# 09-other.net
KiCad netlist of a schematic drawn in Altium Designer
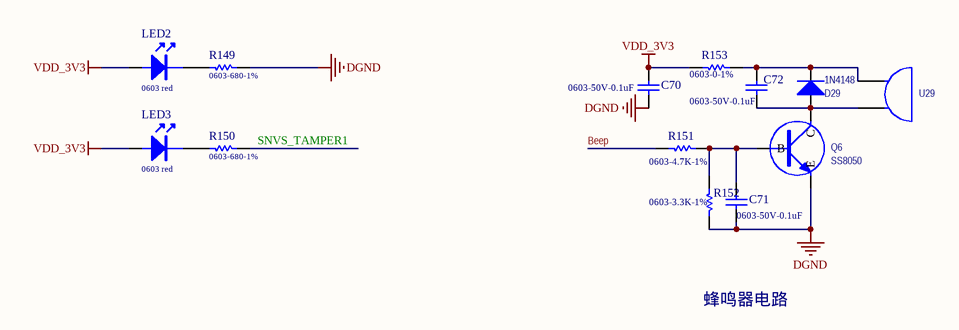
[diagram p0: 09-other.SchDoc]

(export (version "E")
  (design (tool "Eeschema 10.0.6"))
  (components
    (comp (ref "C70")
      (value "0603-50V-0.1uF")
      (footprint "0603C")
      (description "Capacitor")
      (fields (field (name "PUBLISHER") "Altium Limited"))
      (libsource (lib "Miscellaneous Devices") (part "Cap"))
    )
    (comp (ref "C71")
      (value "0603-50V-0.1uF")
      (footprint "0603C")
      (description "Capacitor")
      (fields (field (name "PUBLISHER") "Altium Limited"))
      (libsource (lib "Miscellaneous Devices") (part "Cap"))
    )
    (comp (ref "C72")
      (value "0603-50V-0.1uF")
      (footprint "0603C")
      (description "Capacitor")
      (fields (field (name "PUBLISHER") "Altium Limited"))
      (libsource (lib "Miscellaneous Devices") (part "Cap"))
    )
    (comp (ref "D29")
      (value "1N4148")
      (footprint "SOD-323")
      (description "High Conductance Fast Diode")
      (fields (field (name "PUBLISHER") "Altium Limited"))
      (libsource (lib "Miscellaneous Devices") (part "Diode 1N4148"))
    )
    (comp (ref "LED2") (value "0603 red") (footprint "LED_1") (libsource (lib "RC-sheet") (part "LED")))
    (comp (ref "LED3") (value "0603 red") (footprint "LED_1") (libsource (lib "RC-sheet") (part "LED")))
    (comp (ref "Q6")
      (value "SS8050")
      (footprint "SOT-23")
      (description "NPN Transistor")
      (libsource (lib "RC-sheet") (part "NPN"))
    )
    (comp (ref "R149")
      (value "0603-680-1%")
      (footprint "0603R")
      (description "Resistor")
      (fields (field (name "PUBLISHER") "Altium Limited"))
      (libsource (lib "Miscellaneous Devices") (part "Res1"))
    )
    (comp (ref "R150")
      (value "0603-680-1%")
      (footprint "0603R")
      (description "Resistor")
      (fields (field (name "PUBLISHER") "Altium Limited"))
      (libsource (lib "Miscellaneous Devices") (part "Res1"))
    )
    (comp (ref "R151")
      (value "0603-4.7K-1%")
      (footprint "0603R")
      (description "Resistor")
      (fields (field (name "PUBLISHER") "Altium Limited"))
      (libsource (lib "Miscellaneous Devices") (part "Res1"))
    )
    (comp (ref "R152")
      (value "0603-3.3K-1%")
      (footprint "0603R")
      (description "Resistor")
      (fields (field (name "PUBLISHER") "Altium Limited"))
      (libsource (lib "Miscellaneous Devices") (part "Res1"))
    )
    (comp (ref "R153")
      (value "0603-0-1%")
      (footprint "0603R")
      (description "Resistor")
      (fields (field (name "PUBLISHER") "Altium Limited"))
      (libsource (lib "Miscellaneous Devices") (part "Res1"))
    )
    (comp (ref "U29")
      (value "BUZZER")
      (footprint "B-12*9.5")
      (description "TMB12A03")
      (libsource (lib "RC-sheet") (part "BUZZER"))
    )
  )
  (nets
    (net (code "1") (name "/Beep") (class "Default")
      (node (ref "R151") (pin "1") (pinfunction "1_1") (pintype "passive"))
    )
    (net (code "2") (name "/SNVS_TAMPER1") (class "Default")
      (node (ref "R150") (pin "1") (pinfunction "1_1") (pintype "passive"))
    )
    (net (code "3") (name "DGND") (class "Default")
      (node (ref "C70") (pin "2") (pinfunction "2_2") (pintype "passive"))
      (node (ref "C71") (pin "2") (pinfunction "2_2") (pintype "passive"))
      (node (ref "Q6") (pin "2") (pinfunction "E_2") (pintype "passive"))
      (node (ref "R149") (pin "1") (pinfunction "1_1") (pintype "passive"))
      (node (ref "R152") (pin "1") (pinfunction "1_1") (pintype "passive"))
    )
    (net (code "4") (name "Net-(D29-A)") (class "Default")
      (node (ref "C72") (pin "2") (pinfunction "2_2") (pintype "passive"))
      (node (ref "D29") (pin "1") (pinfunction "A_1") (pintype "passive"))
      (node (ref "Q6") (pin "3") (pinfunction "C_3") (pintype "passive"))
      (node (ref "U29") (pin "2") (pinfunction "B_2") (pintype "passive"))
    )
    (net (code "5") (name "Net-(D29-K)") (class "Default")
      (node (ref "C72") (pin "1") (pinfunction "1_1") (pintype "passive"))
      (node (ref "D29") (pin "2") (pinfunction "K_2") (pintype "passive"))
      (node (ref "R153") (pin "1") (pinfunction "1_1") (pintype "passive"))
      (node (ref "U29") (pin "1") (pinfunction "A_1") (pintype "passive"))
    )
    (net (code "6") (name "Net-(LED2-Pad2)") (class "Default")
      (node (ref "LED2") (pin "2") (pinfunction "2_2") (pintype "passive"))
      (node (ref "R149") (pin "2") (pinfunction "2_2") (pintype "passive"))
    )
    (net (code "7") (name "Net-(LED3-Pad2)") (class "Default")
      (node (ref "LED3") (pin "2") (pinfunction "2_2") (pintype "passive"))
      (node (ref "R150") (pin "2") (pinfunction "2_2") (pintype "passive"))
    )
    (net (code "8") (name "Net-(Q6-B)") (class "Default")
      (node (ref "C71") (pin "1") (pinfunction "1_1") (pintype "passive"))
      (node (ref "Q6") (pin "1") (pinfunction "B_1") (pintype "passive"))
      (node (ref "R151") (pin "2") (pinfunction "2_2") (pintype "passive"))
      (node (ref "R152") (pin "2") (pinfunction "2_2") (pintype "passive"))
    )
    (net (code "9") (name "VDD_3V3") (class "Default")
      (node (ref "C70") (pin "1") (pinfunction "1_1") (pintype "passive"))
      (node (ref "LED2") (pin "1") (pinfunction "1_1") (pintype "passive"))
      (node (ref "LED3") (pin "1") (pinfunction "1_1") (pintype "passive"))
      (node (ref "R153") (pin "2") (pinfunction "2_2") (pintype "passive"))
    )
  )
)
